# PowerSupply.net
KiCad netlist of a schematic drawn in EAGLE
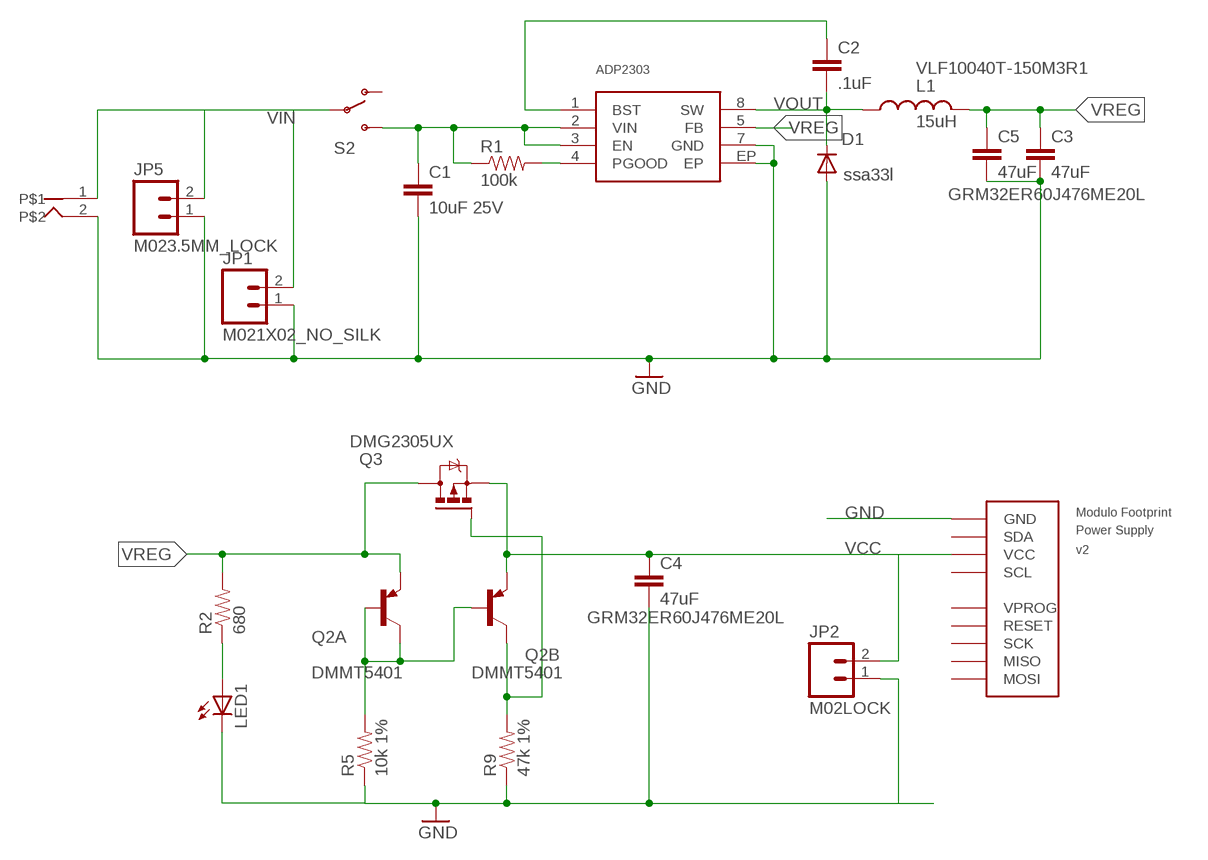
[diagram p0: schematic, sheet 1]

(export (version "E")
  (design (tool "Eeschema 10.0.6"))
  (components
    (comp (ref "C1")
      (value "10uF 25V")
      (footprint "eagle-import:0805")
      (libsource (lib "eagle-import") (part "CAP0805"))
    )
    (comp (ref "C2")
      (value ".1uF")
      (footprint "eagle-import:0805")
      (libsource (lib "eagle-import") (part "CAP0805"))
    )
    (comp (ref "C3")
      (value "47uF")
      (footprint "eagle-import:1210")
      (libsource (lib "eagle-import") (part "CAP1210"))
    )
    (comp (ref "C4")
      (value "47uF")
      (footprint "eagle-import:1210")
      (libsource (lib "eagle-import") (part "CAP1210"))
    )
    (comp (ref "C5")
      (value "47uF")
      (footprint "eagle-import:1210")
      (libsource (lib "eagle-import") (part "CAP1210"))
    )
    (comp (ref "D1")
      (value "ssa33l")
      (footprint "eagle-import:SMA-DIODE")
      (libsource (lib "eagle-import") (part "DIODESMA"))
    )
    (comp (ref "JP1")
      (value "M021X02_NO_SILK")
      (footprint "eagle-import:1X02_NO_SILK")
      (libsource (lib "eagle-import") (part "M021X02_NO_SILK"))
    )
    (comp (ref "JP2")
      (value "M02LOCK")
      (footprint "eagle-import:1X02_LOCK")
      (libsource (lib "eagle-import") (part "M02LOCK"))
    )
    (comp (ref "JP5")
      (value "M023.5MM_LOCK")
      (footprint "eagle-import:SCREWTERMINAL-3.5MM-2_LOCK")
      (libsource (lib "eagle-import") (part "M023.5MM_LOCK"))
    )
    (comp (ref "L1")
      (value "15uH")
      (footprint "eagle-import:INDUCTOR-VLF10040")
      (libsource (lib "eagle-import") (part "INDUCTORVLF10040"))
    )
    (comp (ref "LED1")
      (value "LEDCHIP-LED0805")
      (footprint "eagle-import:CHIP-LED0805")
      (libsource (lib "eagle-import") (part "LEDCHIP-LED0805"))
    )
    (comp (ref "Q2")
      (value "DMMT5401")
      (footprint "eagle-import:SOT-26")
      (libsource (lib "eagle-import") (part "TRANSISTOR-DUAL-PNP"))
    )
    (comp (ref "Q3")
      (value "DMG2305UX")
      (footprint "eagle-import:MICRO3")
      (libsource (lib "eagle-import") (part "IRLML5203"))
    )
    (comp (ref "R1")
      (value "100k")
      (footprint "eagle-import:0805")
      (libsource (lib "eagle-import") (part "SparkFun-Resistors_RESISTOR0805-RES"))
    )
    (comp (ref "R2")
      (value "680")
      (footprint "eagle-import:0805")
      (libsource (lib "eagle-import") (part "RESISTOR0805-RES"))
    )
    (comp (ref "R5")
      (value "10k 1%")
      (footprint "eagle-import:0805")
      (libsource (lib "eagle-import") (part "RESISTOR0805-RES"))
    )
    (comp (ref "R9")
      (value "47k 1%")
      (footprint "eagle-import:0805")
      (libsource (lib "eagle-import") (part "RESISTOR0805-RES"))
    )
    (comp (ref "S2")
      (value "SWITCH-SPDTPTH_LOCK")
      (footprint "eagle-import:SWITCH-SPDT_LOCK.007S")
      (libsource (lib "eagle-import") (part "SWITCH-SPDTPTH_LOCK"))
    )
    (comp (ref "U$3")
      (value "ADP2303")
      (footprint "eagle-import:SOIC8-EP")
      (libsource (lib "eagle-import") (part "ADP2303"))
    )
    (comp (ref "U$4")
      (value "FOOTPRINTFOOTPRINT-2")
      (footprint "eagle-import:FOOTPRINT2")
      (fields (field (name "BOARD") "Power Supply") (field (name "VERSION") "v2"))
      (libsource (lib "eagle-import") (part "FOOTPRINTFOOTPRINT-2"))
    )
    (comp (ref "U$21")
      (value "DC-JACKLOWPRO")
      (footprint "eagle-import:DC-POWER-JACK-LOWPRO")
      (libsource (lib "eagle-import") (part "DC-JACKLOWPRO"))
    )
  )
  (nets
    (net (code "1") (name "/VCC") (class "Default")
      (node (ref "C4") (pin "1") (pinfunction "1_1") (pintype "passive"))
      (node (ref "JP2") (pin "2") (pinfunction "2_2") (pintype "passive"))
      (node (ref "Q2") (pin "5") (pinfunction "E_5") (pintype "passive"))
      (node (ref "Q3") (pin "2") (pinfunction "S_2") (pintype "passive"))
      (node (ref "U$4") (pin "BUS2") (pinfunction "VCC_BUS2") (pintype "bidirectional"))
    )
    (net (code "2") (name "/VIN") (class "Default")
      (node (ref "C1") (pin "1") (pinfunction "1_1") (pintype "passive"))
      (node (ref "R1") (pin "1") (pinfunction "1_1") (pintype "passive"))
      (node (ref "S2") (pin "3") (pinfunction "S_3") (pintype "passive"))
      (node (ref "U$3") (pin "2") (pinfunction "VIN_2") (pintype "bidirectional"))
      (node (ref "U$3") (pin "3") (pinfunction "EN_3") (pintype "bidirectional"))
    )
    (net (code "3") (name "/VOUT") (class "Default")
      (node (ref "C2") (pin "2") (pinfunction "2_2") (pintype "passive"))
      (node (ref "D1") (pin "C") (pinfunction "C_C") (pintype "passive"))
      (node (ref "L1") (pin "P$1") (pinfunction "1_P$1") (pintype "passive"))
      (node (ref "U$3") (pin "8") (pinfunction "SW_8") (pintype "bidirectional"))
    )
    (net (code "4") (name "GND") (class "Default")
      (node (ref "C1") (pin "2") (pinfunction "2_2") (pintype "passive"))
      (node (ref "C3") (pin "2") (pinfunction "2_2") (pintype "passive"))
      (node (ref "C4") (pin "2") (pinfunction "2_2") (pintype "passive"))
      (node (ref "C5") (pin "2") (pinfunction "2_2") (pintype "passive"))
      (node (ref "D1") (pin "A") (pinfunction "A_A") (pintype "passive"))
      (node (ref "JP1") (pin "1") (pinfunction "1_1") (pintype "passive"))
      (node (ref "JP2") (pin "1") (pinfunction "1_1") (pintype "passive"))
      (node (ref "JP5") (pin "1") (pinfunction "1_1") (pintype "passive"))
      (node (ref "LED1") (pin "C") (pinfunction "C_C") (pintype "passive"))
      (node (ref "R5") (pin "1") (pinfunction "1_1") (pintype "passive"))
      (node (ref "R9") (pin "1") (pinfunction "1_1") (pintype "passive"))
      (node (ref "U$21") (pin "2") (pinfunction "P$2_2") (pintype "bidirectional"))
      (node (ref "U$3") (pin "7") (pinfunction "GND_7") (pintype "bidirectional"))
      (node (ref "U$3") (pin "EP") (pinfunction "EP_EP") (pintype "bidirectional"))
      (node (ref "U$4") (pin "BUS0") (pinfunction "GND_BUS0") (pintype "bidirectional"))
    )
    (net (code "5") (name "Net-(LED1-PadA)") (class "Default")
      (node (ref "LED1") (pin "A") (pinfunction "A_A") (pintype "passive"))
      (node (ref "R2") (pin "1") (pinfunction "1_1") (pintype "passive"))
    )
    (net (code "6") (name "Net-(Q2A-B)") (class "Default")
      (node (ref "Q2") (pin "1") (pinfunction "C_1") (pintype "passive"))
      (node (ref "Q2") (pin "2") (pinfunction "B_2") (pintype "passive"))
      (node (ref "Q2") (pin "3") (pinfunction "B_3") (pintype "passive"))
      (node (ref "R5") (pin "2") (pinfunction "2_2") (pintype "passive"))
    )
    (net (code "7") (name "Net-(Q2B-C)") (class "Default")
      (node (ref "Q2") (pin "4") (pinfunction "C_4") (pintype "passive"))
      (node (ref "Q3") (pin "1") (pinfunction "G_1") (pintype "passive"))
      (node (ref "R9") (pin "2") (pinfunction "2_2") (pintype "passive"))
    )
    (net (code "8") (name "Net-(S2-P)") (class "Default")
      (node (ref "JP1") (pin "2") (pinfunction "2_2") (pintype "passive"))
      (node (ref "JP5") (pin "2") (pinfunction "2_2") (pintype "passive"))
      (node (ref "S2") (pin "2") (pinfunction "P_2") (pintype "passive"))
      (node (ref "U$21") (pin "1") (pinfunction "P$1_1") (pintype "bidirectional"))
    )
    (net (code "9") (name "Net-(U$3-BST)") (class "Default")
      (node (ref "C2") (pin "1") (pinfunction "1_1") (pintype "passive"))
      (node (ref "U$3") (pin "1") (pinfunction "BST_1") (pintype "bidirectional"))
    )
    (net (code "10") (name "Net-(U$3-PGOOD)") (class "Default")
      (node (ref "R1") (pin "2") (pinfunction "2_2") (pintype "passive"))
      (node (ref "U$3") (pin "4") (pinfunction "PGOOD_4") (pintype "bidirectional"))
    )
    (net (code "11") (name "VREG") (class "Default")
      (node (ref "C3") (pin "1") (pinfunction "1_1") (pintype "passive"))
      (node (ref "C5") (pin "1") (pinfunction "1_1") (pintype "passive"))
      (node (ref "L1") (pin "P$2") (pinfunction "2_P$2") (pintype "passive"))
      (node (ref "Q2") (pin "6") (pinfunction "E_6") (pintype "passive"))
      (node (ref "Q3") (pin "3") (pinfunction "D_3") (pintype "passive"))
      (node (ref "R2") (pin "2") (pinfunction "2_2") (pintype "passive"))
      (node (ref "U$3") (pin "5") (pinfunction "FB_5") (pintype "bidirectional"))
    )
    (net (code "12") (name "unconnected-(S2-O-Pad1)") (class "Default")
      (node (ref "S2") (pin "1") (pinfunction "O_1") (pintype "passive"))
    )
    (net (code "13") (name "unconnected-(U$4-MISO-PadPROG3)") (class "Default")
      (node (ref "U$4") (pin "PROG3") (pinfunction "MISO_PROG3") (pintype "bidirectional"))
    )
    (net (code "14") (name "unconnected-(U$4-MOSI-PadPROG4)") (class "Default")
      (node (ref "U$4") (pin "PROG4") (pinfunction "MOSI_PROG4") (pintype "bidirectional"))
    )
    (net (code "15") (name "unconnected-(U$4-RESET-PadPROG1)") (class "Default")
      (node (ref "U$4") (pin "PROG1") (pinfunction "RESET_PROG1") (pintype "bidirectional"))
    )
    (net (code "16") (name "unconnected-(U$4-SCK-PadPROG2)") (class "Default")
      (node (ref "U$4") (pin "PROG2") (pinfunction "SCK_PROG2") (pintype "bidirectional"))
    )
    (net (code "17") (name "unconnected-(U$4-SCL-PadBUS3)") (class "Default")
      (node (ref "U$4") (pin "BUS3") (pinfunction "SCL_BUS3") (pintype "bidirectional"))
    )
    (net (code "18") (name "unconnected-(U$4-SDA-PadBUS1)") (class "Default")
      (node (ref "U$4") (pin "BUS1") (pinfunction "SDA_BUS1") (pintype "bidirectional"))
    )
    (net (code "19") (name "unconnected-(U$4-VPROG-PadPROG0)") (class "Default")
      (node (ref "U$4") (pin "PROG0") (pinfunction "VPROG_PROG0") (pintype "bidirectional"))
    )
  )
)
